# PERIPHERALS.net
KiCad netlist of a schematic drawn in Altium Designer
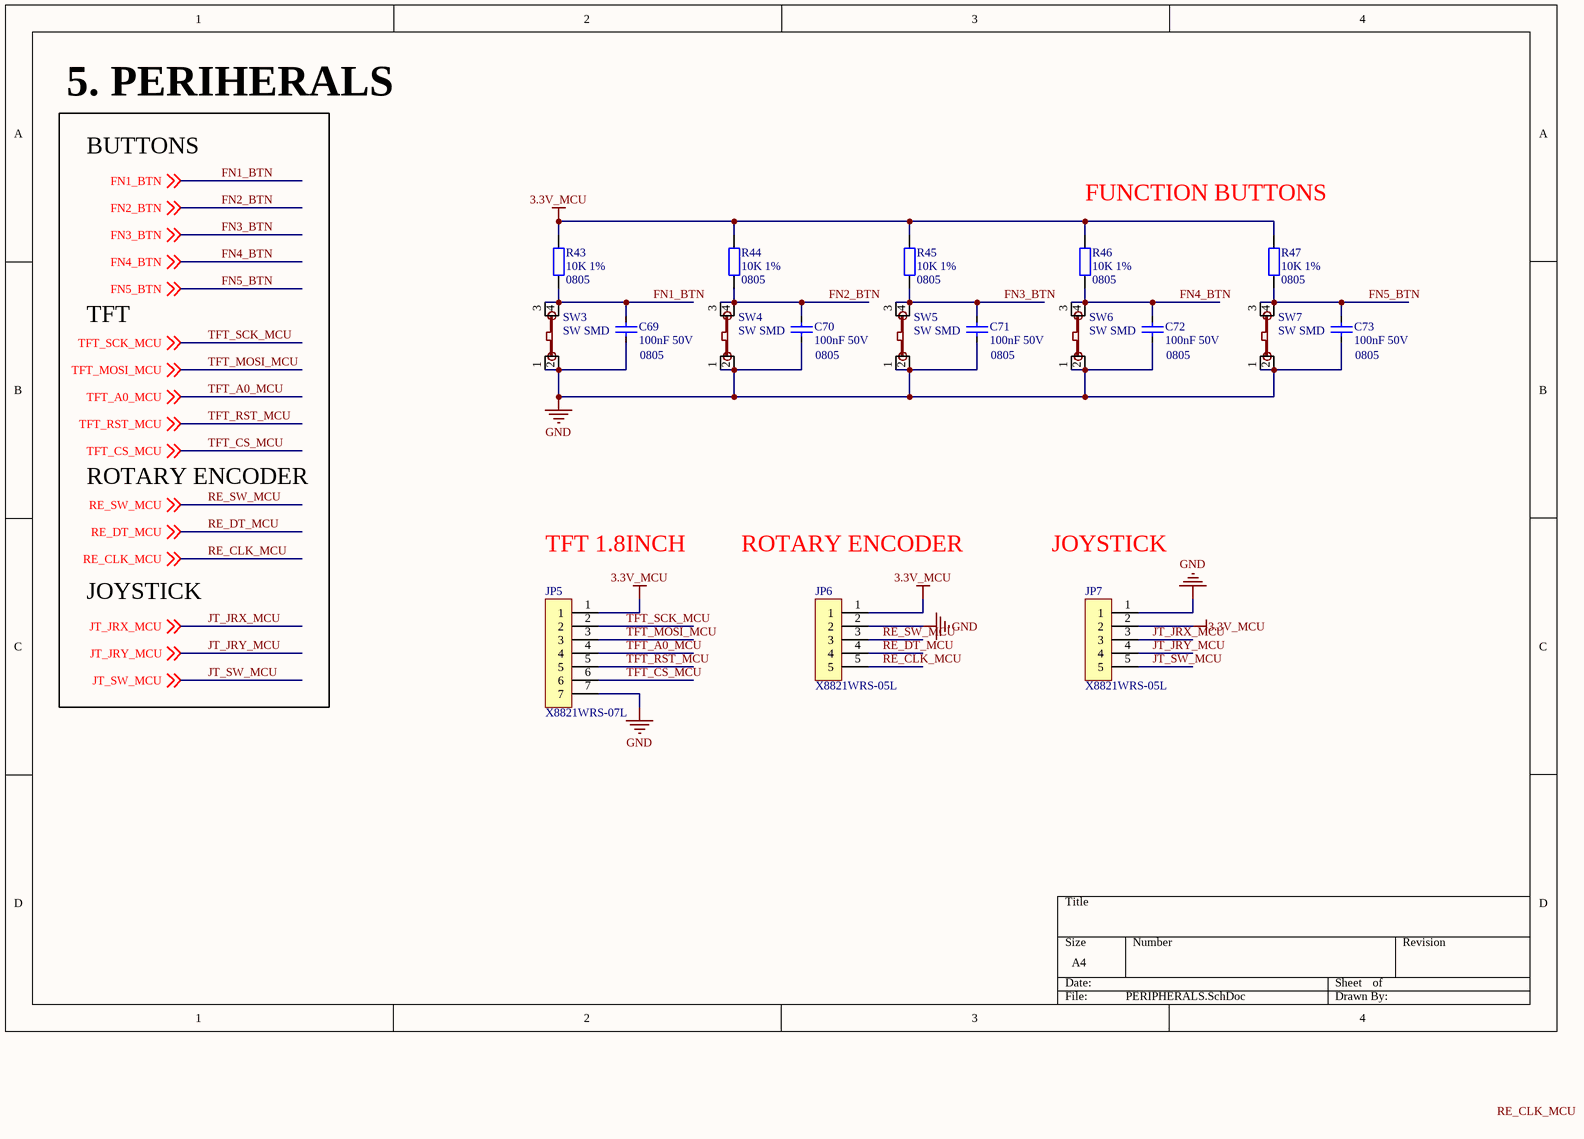
[diagram p0: PERIPHERALS.SchDoc]

(export (version "E")
  (design (tool "Eeschema 10.0.6"))
  (components
    (comp (ref "C69")
      (value "100nF 50V")
      (footprint "CAP_SMD_0805")
      (description "0.1 µF ±10% 50V Ceramic Capacitor X7R 0805 (2012 Metric)")
      (fields
        (field (name "MANUFACTURER") "YAGEO")
        (field (name "MANUFACTURE PART NUMBER") "CC0805KRX7R9BB104")
        (field (name "SIZE") "0805")
      )
      (libsource (lib "Capacitors") (part "C0805_MLCC_100nF_50V"))
    )
    (comp (ref "C70")
      (value "100nF 50V")
      (footprint "CAP_SMD_0805")
      (description "0.1 µF ±10% 50V Ceramic Capacitor X7R 0805 (2012 Metric)")
      (fields
        (field (name "MANUFACTURER") "YAGEO")
        (field (name "MANUFACTURE PART NUMBER") "CC0805KRX7R9BB104")
        (field (name "SIZE") "0805")
      )
      (libsource (lib "Capacitors") (part "C0805_MLCC_100nF_50V"))
    )
    (comp (ref "C71")
      (value "100nF 50V")
      (footprint "CAP_SMD_0805")
      (description "0.1 µF ±10% 50V Ceramic Capacitor X7R 0805 (2012 Metric)")
      (fields
        (field (name "MANUFACTURER") "YAGEO")
        (field (name "MANUFACTURE PART NUMBER") "CC0805KRX7R9BB104")
        (field (name "SIZE") "0805")
      )
      (libsource (lib "Capacitors") (part "C0805_MLCC_100nF_50V"))
    )
    (comp (ref "C72")
      (value "100nF 50V")
      (footprint "CAP_SMD_0805")
      (description "0.1 µF ±10% 50V Ceramic Capacitor X7R 0805 (2012 Metric)")
      (fields
        (field (name "MANUFACTURER") "YAGEO")
        (field (name "MANUFACTURE PART NUMBER") "CC0805KRX7R9BB104")
        (field (name "SIZE") "0805")
      )
      (libsource (lib "Capacitors") (part "C0805_MLCC_100nF_50V"))
    )
    (comp (ref "C73")
      (value "100nF 50V")
      (footprint "CAP_SMD_0805")
      (description "0.1 µF ±10% 50V Ceramic Capacitor X7R 0805 (2012 Metric)")
      (fields
        (field (name "MANUFACTURER") "YAGEO")
        (field (name "MANUFACTURE PART NUMBER") "CC0805KRX7R9BB104")
        (field (name "SIZE") "0805")
      )
      (libsource (lib "Capacitors") (part "C0805_MLCC_100nF_50V"))
    )
    (comp (ref "JP5")
      (value "X8821WRS-07L")
      (footprint "CONN_X8821WRS-07L-LPSN")
      (fields
        (field (name "MANUFACTURER") "XKB Connection")
        (field (name "MANUFACTURE PART NUMBER") "X8821WRS-07-9TSN")
      )
      (libsource (lib "Connectors") (part "X8821WRS-07L"))
    )
    (comp (ref "JP6")
      (value "X8821WRS-05L")
      (footprint "CONN_X8821WRS-05L-LPSN")
      (fields
        (field (name "MANUFACTURER") "XKB Connection")
        (field (name "MANUFACTURE PART NUMBER") "X8821WRS-05-9TSN")
      )
      (libsource (lib "Connectors") (part "X8821WRS-05L"))
    )
    (comp (ref "JP7")
      (value "X8821WRS-05L")
      (footprint "CONN_X8821WRS-05L-LPSN")
      (fields
        (field (name "MANUFACTURER") "XKB Connection")
        (field (name "MANUFACTURE PART NUMBER") "X8821WRS-05-9TSN")
      )
      (libsource (lib "Connectors") (part "X8821WRS-05L"))
    )
    (comp (ref "R43")
      (value "10K 1%")
      (footprint "RES_SMD_0805")
      (description "10 kOhms ±1% 0.125W, 1/8W Chip Resistor 0805 (2012 Metric) Moisture Resistant Thick Film")
      (fields
        (field (name "MANUFACTURER") "YAGEO")
        (field (name "MANUFACTURE PART NUMBER") "RC0805FR-0710KL")
        (field (name "SIZE") "0805")
      )
      (libsource (lib "Resistors") (part "R0805_10K"))
    )
    (comp (ref "R44")
      (value "10K 1%")
      (footprint "RES_SMD_0805")
      (description "10 kOhms ±1% 0.125W, 1/8W Chip Resistor 0805 (2012 Metric) Moisture Resistant Thick Film")
      (fields
        (field (name "MANUFACTURER") "YAGEO")
        (field (name "MANUFACTURE PART NUMBER") "RC0805FR-0710KL")
        (field (name "SIZE") "0805")
      )
      (libsource (lib "Resistors") (part "R0805_10K"))
    )
    (comp (ref "R45")
      (value "10K 1%")
      (footprint "RES_SMD_0805")
      (description "10 kOhms ±1% 0.125W, 1/8W Chip Resistor 0805 (2012 Metric) Moisture Resistant Thick Film")
      (fields
        (field (name "MANUFACTURER") "YAGEO")
        (field (name "MANUFACTURE PART NUMBER") "RC0805FR-0710KL")
        (field (name "SIZE") "0805")
      )
      (libsource (lib "Resistors") (part "R0805_10K"))
    )
    (comp (ref "R46")
      (value "10K 1%")
      (footprint "RES_SMD_0805")
      (description "10 kOhms ±1% 0.125W, 1/8W Chip Resistor 0805 (2012 Metric) Moisture Resistant Thick Film")
      (fields
        (field (name "MANUFACTURER") "YAGEO")
        (field (name "MANUFACTURE PART NUMBER") "RC0805FR-0710KL")
        (field (name "SIZE") "0805")
      )
      (libsource (lib "Resistors") (part "R0805_10K"))
    )
    (comp (ref "R47")
      (value "10K 1%")
      (footprint "RES_SMD_0805")
      (description "10 kOhms ±1% 0.125W, 1/8W Chip Resistor 0805 (2012 Metric) Moisture Resistant Thick Film")
      (fields
        (field (name "MANUFACTURER") "YAGEO")
        (field (name "MANUFACTURE PART NUMBER") "RC0805FR-0710KL")
        (field (name "SIZE") "0805")
      )
      (libsource (lib "Resistors") (part "R0805_10K"))
    )
    (comp (ref "SW3")
      (value "SW SMD")
      (footprint "SMD_6X6X7")
      (description "不带 6mm 7mm 50mA Round Button Brick nogging SPST 6mm 8万次 12V SMD Tactile Switches ROHS")
      (fields
        (field (name "MANUFACTURER") "Shenzhen Kinghelm Elec")
        (field (name "MANUFACTURE PART NUMBER") "KH-6X6X7H-STM")
      )
      (libsource (lib "Button") (part "SW_SMD_6X6X7"))
    )
    (comp (ref "SW4")
      (value "SW SMD")
      (footprint "SMD_6X6X7")
      (description "不带 6mm 7mm 50mA Round Button Brick nogging SPST 6mm 8万次 12V SMD Tactile Switches ROHS")
      (fields
        (field (name "MANUFACTURER") "Shenzhen Kinghelm Elec")
        (field (name "MANUFACTURE PART NUMBER") "KH-6X6X7H-STM")
      )
      (libsource (lib "Button") (part "SW_SMD_6X6X7"))
    )
    (comp (ref "SW5")
      (value "SW SMD")
      (footprint "SMD_6X6X7")
      (description "不带 6mm 7mm 50mA Round Button Brick nogging SPST 6mm 8万次 12V SMD Tactile Switches ROHS")
      (fields
        (field (name "MANUFACTURER") "Shenzhen Kinghelm Elec")
        (field (name "MANUFACTURE PART NUMBER") "KH-6X6X7H-STM")
      )
      (libsource (lib "Button") (part "SW_SMD_6X6X7"))
    )
    (comp (ref "SW6")
      (value "SW SMD")
      (footprint "SMD_6X6X7")
      (description "不带 6mm 7mm 50mA Round Button Brick nogging SPST 6mm 8万次 12V SMD Tactile Switches ROHS")
      (fields
        (field (name "MANUFACTURER") "Shenzhen Kinghelm Elec")
        (field (name "MANUFACTURE PART NUMBER") "KH-6X6X7H-STM")
      )
      (libsource (lib "Button") (part "SW_SMD_6X6X7"))
    )
    (comp (ref "SW7")
      (value "SW SMD")
      (footprint "SMD_6X6X7")
      (description "不带 6mm 7mm 50mA Round Button Brick nogging SPST 6mm 8万次 12V SMD Tactile Switches ROHS")
      (fields
        (field (name "MANUFACTURER") "Shenzhen Kinghelm Elec")
        (field (name "MANUFACTURE PART NUMBER") "KH-6X6X7H-STM")
      )
      (libsource (lib "Button") (part "SW_SMD_6X6X7"))
    )
  )
  (nets
    (net (code "1") (name "3.3V_MCU") (class "Default")
      (node (ref "JP5") (pin "1") (pinfunction "1_1") (pintype "passive"))
      (node (ref "JP6") (pin "1") (pinfunction "1_1") (pintype "passive"))
      (node (ref "JP7") (pin "2") (pinfunction "2_2") (pintype "passive"))
      (node (ref "R43") (pin "2") (pinfunction "2_2") (pintype "passive"))
      (node (ref "R44") (pin "2") (pinfunction "2_2") (pintype "passive"))
      (node (ref "R45") (pin "2") (pinfunction "2_2") (pintype "passive"))
      (node (ref "R46") (pin "2") (pinfunction "2_2") (pintype "passive"))
      (node (ref "R47") (pin "2") (pinfunction "2_2") (pintype "passive"))
    )
    (net (code "2") (name "FN1_BTN") (class "Default")
      (node (ref "C69") (pin "2") (pinfunction "2_2") (pintype "passive"))
      (node (ref "R43") (pin "1") (pinfunction "1_1") (pintype "passive"))
      (node (ref "SW3") (pin "3") (pinfunction "3_3") (pintype "passive"))
      (node (ref "SW3") (pin "4") (pinfunction "4_4") (pintype "passive"))
    )
    (net (code "3") (name "FN2_BTN") (class "Default")
      (node (ref "C70") (pin "2") (pinfunction "2_2") (pintype "passive"))
      (node (ref "R44") (pin "1") (pinfunction "1_1") (pintype "passive"))
      (node (ref "SW4") (pin "3") (pinfunction "3_3") (pintype "passive"))
      (node (ref "SW4") (pin "4") (pinfunction "4_4") (pintype "passive"))
    )
    (net (code "4") (name "FN3_BTN") (class "Default")
      (node (ref "C71") (pin "2") (pinfunction "2_2") (pintype "passive"))
      (node (ref "R45") (pin "1") (pinfunction "1_1") (pintype "passive"))
      (node (ref "SW5") (pin "3") (pinfunction "3_3") (pintype "passive"))
      (node (ref "SW5") (pin "4") (pinfunction "4_4") (pintype "passive"))
    )
    (net (code "5") (name "FN4_BTN") (class "Default")
      (node (ref "C72") (pin "2") (pinfunction "2_2") (pintype "passive"))
      (node (ref "R46") (pin "1") (pinfunction "1_1") (pintype "passive"))
      (node (ref "SW6") (pin "3") (pinfunction "3_3") (pintype "passive"))
      (node (ref "SW6") (pin "4") (pinfunction "4_4") (pintype "passive"))
    )
    (net (code "6") (name "FN5_BTN") (class "Default")
      (node (ref "C73") (pin "2") (pinfunction "2_2") (pintype "passive"))
      (node (ref "R47") (pin "1") (pinfunction "1_1") (pintype "passive"))
      (node (ref "SW7") (pin "3") (pinfunction "3_3") (pintype "passive"))
      (node (ref "SW7") (pin "4") (pinfunction "4_4") (pintype "passive"))
    )
    (net (code "7") (name "GND") (class "Default")
      (node (ref "C69") (pin "1") (pinfunction "1_1") (pintype "passive"))
      (node (ref "C70") (pin "1") (pinfunction "1_1") (pintype "passive"))
      (node (ref "C71") (pin "1") (pinfunction "1_1") (pintype "passive"))
      (node (ref "C72") (pin "1") (pinfunction "1_1") (pintype "passive"))
      (node (ref "C73") (pin "1") (pinfunction "1_1") (pintype "passive"))
      (node (ref "JP5") (pin "7") (pinfunction "7_7") (pintype "passive"))
      (node (ref "JP6") (pin "2") (pinfunction "2_2") (pintype "passive"))
      (node (ref "JP7") (pin "1") (pinfunction "1_1") (pintype "passive"))
      (node (ref "SW3") (pin "1") (pinfunction "1_1") (pintype "passive"))
      (node (ref "SW3") (pin "2") (pinfunction "2_2") (pintype "passive"))
      (node (ref "SW4") (pin "1") (pinfunction "1_1") (pintype "passive"))
      (node (ref "SW4") (pin "2") (pinfunction "2_2") (pintype "passive"))
      (node (ref "SW5") (pin "1") (pinfunction "1_1") (pintype "passive"))
      (node (ref "SW5") (pin "2") (pinfunction "2_2") (pintype "passive"))
      (node (ref "SW6") (pin "1") (pinfunction "1_1") (pintype "passive"))
      (node (ref "SW6") (pin "2") (pinfunction "2_2") (pintype "passive"))
      (node (ref "SW7") (pin "1") (pinfunction "1_1") (pintype "passive"))
      (node (ref "SW7") (pin "2") (pinfunction "2_2") (pintype "passive"))
    )
    (net (code "8") (name "JT_JRX_MCU") (class "Default")
      (node (ref "JP7") (pin "3") (pinfunction "3_3") (pintype "passive"))
    )
    (net (code "9") (name "JT_JRY_MCU") (class "Default")
      (node (ref "JP7") (pin "4") (pinfunction "4_4") (pintype "passive"))
    )
    (net (code "10") (name "JT_SW_MCU") (class "Default")
      (node (ref "JP7") (pin "5") (pinfunction "5_5") (pintype "passive"))
    )
    (net (code "11") (name "RE_CLK_MCU") (class "Default")
      (node (ref "JP6") (pin "5") (pinfunction "5_5") (pintype "passive"))
    )
    (net (code "12") (name "RE_DT_MCU") (class "Default")
      (node (ref "JP6") (pin "4") (pinfunction "4_4") (pintype "passive"))
    )
    (net (code "13") (name "RE_SW_MCU") (class "Default")
      (node (ref "JP6") (pin "3") (pinfunction "3_3") (pintype "passive"))
    )
    (net (code "14") (name "TFT_A0_MCU") (class "Default")
      (node (ref "JP5") (pin "4") (pinfunction "4_4") (pintype "passive"))
    )
    (net (code "15") (name "TFT_CS_MCU") (class "Default")
      (node (ref "JP5") (pin "6") (pinfunction "6_6") (pintype "passive"))
    )
    (net (code "16") (name "TFT_MOSI_MCU") (class "Default")
      (node (ref "JP5") (pin "3") (pinfunction "3_3") (pintype "passive"))
    )
    (net (code "17") (name "TFT_RST_MCU") (class "Default")
      (node (ref "JP5") (pin "5") (pinfunction "5_5") (pintype "passive"))
    )
    (net (code "18") (name "TFT_SCK_MCU") (class "Default")
      (node (ref "JP5") (pin "2") (pinfunction "2_2") (pintype "passive"))
    )
  )
)
